# LED_Module.net
KiCad netlist of a schematic drawn in EAGLE
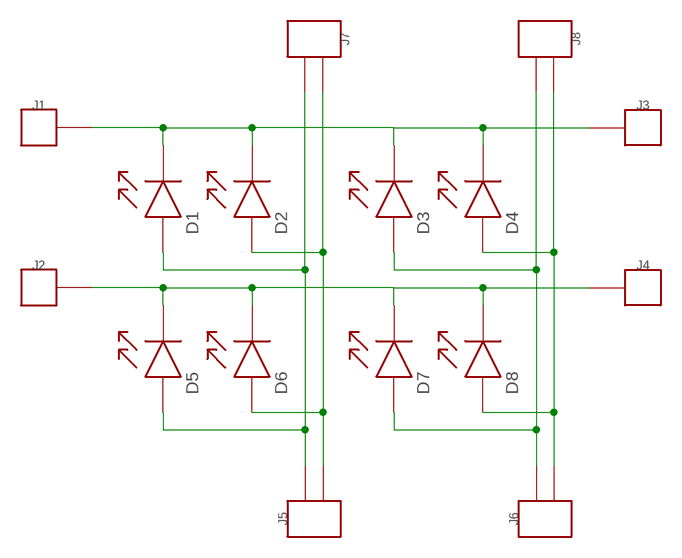
[diagram p0: schematic, sheet 1]

(export (version "E")
  (design (tool "Eeschema 10.0.6"))
  (components
    (comp (ref "D1")
      (value "LED")
      (footprint "eagle-import:0805-POL")
      (libsource (lib "eagle-import") (part "LED"))
    )
    (comp (ref "D2")
      (value "LED")
      (footprint "eagle-import:0805-POL")
      (libsource (lib "eagle-import") (part "LED"))
    )
    (comp (ref "D3")
      (value "LED")
      (footprint "eagle-import:0805-POL")
      (libsource (lib "eagle-import") (part "LED"))
    )
    (comp (ref "D4")
      (value "LED")
      (footprint "eagle-import:0805-POL")
      (libsource (lib "eagle-import") (part "LED"))
    )
    (comp (ref "D5")
      (value "LED")
      (footprint "eagle-import:0805-POL")
      (libsource (lib "eagle-import") (part "LED"))
    )
    (comp (ref "D6")
      (value "LED")
      (footprint "eagle-import:0805-POL")
      (libsource (lib "eagle-import") (part "LED"))
    )
    (comp (ref "D7")
      (value "LED")
      (footprint "eagle-import:0805-POL")
      (libsource (lib "eagle-import") (part "LED"))
    )
    (comp (ref "D8")
      (value "LED")
      (footprint "eagle-import:0805-POL")
      (libsource (lib "eagle-import") (part "LED"))
    )
    (comp (ref "J1")
      (value "LED_JUMPER_1")
      (footprint "eagle-import:LED_JUMPER_1")
      (libsource (lib "eagle-import") (part "LED_JUMPER_1"))
    )
    (comp (ref "J2")
      (value "LED_JUMPER_1")
      (footprint "eagle-import:LED_JUMPER_1")
      (libsource (lib "eagle-import") (part "LED_JUMPER_1"))
    )
    (comp (ref "J3")
      (value "LED_JUMPER_1")
      (footprint "eagle-import:LED_JUMPER_1")
      (libsource (lib "eagle-import") (part "LED_JUMPER_1"))
    )
    (comp (ref "J4")
      (value "LED_JUMPER_1")
      (footprint "eagle-import:LED_JUMPER_1")
      (libsource (lib "eagle-import") (part "LED_JUMPER_1"))
    )
    (comp (ref "J5")
      (value "LED_JUMPER_2")
      (footprint "eagle-import:LED_JUMPER_2")
      (libsource (lib "eagle-import") (part "LED_JUMPER_2"))
    )
    (comp (ref "J6")
      (value "LED_JUMPER_2")
      (footprint "eagle-import:LED_JUMPER_2")
      (libsource (lib "eagle-import") (part "LED_JUMPER_2"))
    )
    (comp (ref "J7")
      (value "LED_JUMPER_2")
      (footprint "eagle-import:LED_JUMPER_2")
      (libsource (lib "eagle-import") (part "LED_JUMPER_2"))
    )
    (comp (ref "J8")
      (value "LED_JUMPER_2")
      (footprint "eagle-import:LED_JUMPER_2")
      (libsource (lib "eagle-import") (part "LED_JUMPER_2"))
    )
  )
  (nets
    (net (code "1") (name "Net-(D1-A)") (class "Default")
      (node (ref "D1") (pin "COM") (pinfunction "A_COM") (pintype "bidirectional"))
      (node (ref "D5") (pin "COM") (pinfunction "A_COM") (pintype "bidirectional"))
      (node (ref "J5") (pin "1") (pinfunction "1_1") (pintype "bidirectional"))
      (node (ref "J7") (pin "2") (pinfunction "2_2") (pintype "bidirectional"))
    )
    (net (code "2") (name "Net-(D1-K)") (class "Default")
      (node (ref "D1") (pin "+") (pinfunction "K_+") (pintype "bidirectional"))
      (node (ref "D2") (pin "+") (pinfunction "K_+") (pintype "bidirectional"))
      (node (ref "D3") (pin "+") (pinfunction "K_+") (pintype "bidirectional"))
      (node (ref "D4") (pin "+") (pinfunction "K_+") (pintype "bidirectional"))
      (node (ref "J1") (pin "1") (pinfunction "1_1") (pintype "bidirectional"))
      (node (ref "J3") (pin "1") (pinfunction "1_1") (pintype "bidirectional"))
    )
    (net (code "3") (name "Net-(D2-A)") (class "Default")
      (node (ref "D2") (pin "COM") (pinfunction "A_COM") (pintype "bidirectional"))
      (node (ref "D6") (pin "COM") (pinfunction "A_COM") (pintype "bidirectional"))
      (node (ref "J5") (pin "2") (pinfunction "2_2") (pintype "bidirectional"))
      (node (ref "J7") (pin "1") (pinfunction "1_1") (pintype "bidirectional"))
    )
    (net (code "4") (name "Net-(D3-A)") (class "Default")
      (node (ref "D3") (pin "COM") (pinfunction "A_COM") (pintype "bidirectional"))
      (node (ref "D7") (pin "COM") (pinfunction "A_COM") (pintype "bidirectional"))
      (node (ref "J6") (pin "1") (pinfunction "1_1") (pintype "bidirectional"))
      (node (ref "J8") (pin "2") (pinfunction "2_2") (pintype "bidirectional"))
    )
    (net (code "5") (name "Net-(D4-A)") (class "Default")
      (node (ref "D4") (pin "COM") (pinfunction "A_COM") (pintype "bidirectional"))
      (node (ref "D8") (pin "COM") (pinfunction "A_COM") (pintype "bidirectional"))
      (node (ref "J6") (pin "2") (pinfunction "2_2") (pintype "bidirectional"))
      (node (ref "J8") (pin "1") (pinfunction "1_1") (pintype "bidirectional"))
    )
    (net (code "6") (name "Net-(D5-K)") (class "Default")
      (node (ref "D5") (pin "+") (pinfunction "K_+") (pintype "bidirectional"))
      (node (ref "D6") (pin "+") (pinfunction "K_+") (pintype "bidirectional"))
      (node (ref "D7") (pin "+") (pinfunction "K_+") (pintype "bidirectional"))
      (node (ref "D8") (pin "+") (pinfunction "K_+") (pintype "bidirectional"))
      (node (ref "J2") (pin "1") (pinfunction "1_1") (pintype "bidirectional"))
      (node (ref "J4") (pin "1") (pinfunction "1_1") (pintype "bidirectional"))
    )
  )
)
